# Pressure_Sensor.net
KiCad netlist of a schematic drawn in Altium Designer
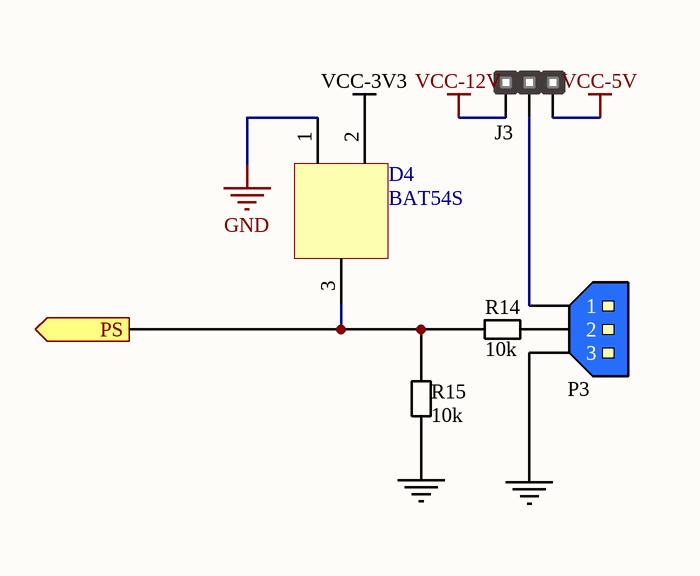
[diagram p0: Pressure_Sensor.SchDoc]

(export (version "E")
  (design (tool "Eeschema 10.0.6"))
  (components
    (comp (ref "D4")
      (value "BAT54S")
      (footprint "BAT54S")
      (libsource (lib "Discrete_Semiconductor") (part "BAT54S"))
    )
    (comp (ref "J3")
      (value "*")
      (footprint "HM1X3")
      (libsource (lib "Electro_Mechanical") (part "HEADER_1x3"))
    )
    (comp (ref "P3")
      (value "TE CONNECTIVITY_3PIN_MALE")
      (footprint "TE CONNECTIVITY_3PIN_MALE")
      (description "BLUE_3PIN_CONECTOR")
      (fields (field (name "MANUFACTURER") "TE CONNECTIVITY / AMP"))
      (libsource (lib "Electro_Mechanical") (part "TE CONNECTIVITY_3PIN_MALE"))
    )
    (comp (ref "R14")
      (value "10k")
      (footprint "RESC2013X38N-0805-NOOVERLAY")
      (description "RES SMD 10 kOhm 1/8W 0805")
      (libsource (lib "Resistors") (part "000001002"))
    )
    (comp (ref "R15")
      (value "10k")
      (footprint "RESC2013X38N-0805-NOOVERLAY")
      (description "RES SMD 10 kOhm 1/8W 0805")
      (libsource (lib "") (part "000001002_1"))
    )
  )
  (nets
    (net (code "1") (name "/PS") (class "Default")
      (node (ref "D4") (pin "3") (pinfunction "3_3") (pintype "passive"))
      (node (ref "R14") (pin "2") (pinfunction "2_2") (pintype "passive"))
      (node (ref "R15") (pin "2") (pinfunction "2_2") (pintype "passive"))
    )
    (net (code "2") (name "GND") (class "Default")
      (node (ref "D4") (pin "1") (pinfunction "1_1") (pintype "passive"))
      (node (ref "P3") (pin "3") (pinfunction "3_3") (pintype "passive"))
      (node (ref "R15") (pin "1") (pinfunction "1_1") (pintype "passive"))
    )
    (net (code "3") (name "Net-(J3-Pad2)") (class "Default")
      (node (ref "J3") (pin "2") (pinfunction "2_2") (pintype "passive"))
      (node (ref "P3") (pin "1") (pinfunction "1_1") (pintype "passive"))
    )
    (net (code "4") (name "Net-(P3-Pad2)") (class "Default")
      (node (ref "P3") (pin "2") (pinfunction "2_2") (pintype "passive"))
      (node (ref "R14") (pin "1") (pinfunction "1_1") (pintype "passive"))
    )
    (net (code "5") (name "VCC-3V3") (class "Default")
      (node (ref "D4") (pin "2") (pinfunction "2_2") (pintype "passive"))
    )
    (net (code "6") (name "VCC-5V") (class "Default")
      (node (ref "J3") (pin "3") (pinfunction "3_3") (pintype "passive"))
    )
    (net (code "7") (name "VCC-12V") (class "Default")
      (node (ref "J3") (pin "1") (pinfunction "1_1") (pintype "passive"))
    )
  )
)
